# Power.net
KiCad netlist of a schematic drawn in Altium Designer
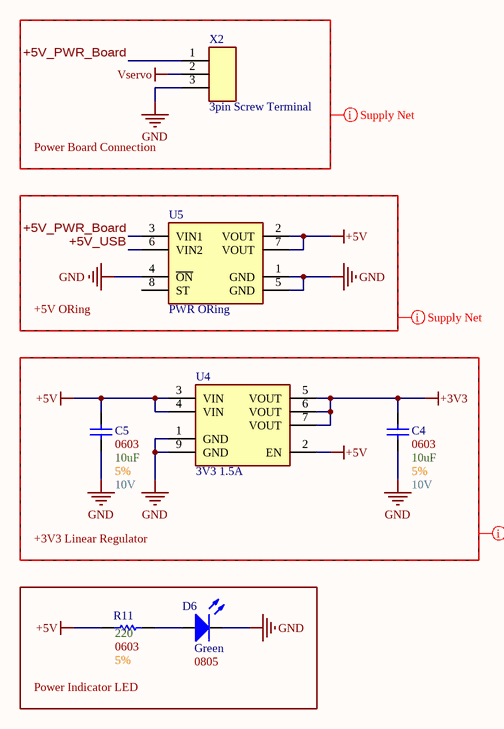
[diagram p0: Power.SchDoc]

(export (version "E")
  (design (tool "Eeschema 10.0.6"))
  (components
    (comp (ref "C4")
      (value "[Cap] SMD Nonpolarized")
      (footprint "[Cap] SMD 0603")
      (fields
        (field (name "SIZE PACKAGE") "0603")
        (field (name "CAPACITANCE") "10uF")
        (field (name "VOLTAGE") "10V")
        (field (name "TOLERANCE") "5%")
      )
      (libsource (lib "RADM Components") (part "[Cap] SMD Nonpolarized"))
    )
    (comp (ref "C5")
      (value "[Cap] SMD Nonpolarized")
      (footprint "[Cap] SMD 0603")
      (fields
        (field (name "SIZE PACKAGE") "0603")
        (field (name "CAPACITANCE") "10uF")
        (field (name "VOLTAGE") "10V")
        (field (name "TOLERANCE") "5%")
      )
      (libsource (lib "RADM Components") (part "[Cap] SMD Nonpolarized"))
    )
    (comp (ref "D6")
      (value "SMD LED")
      (footprint "[LED] SMD 0805")
      (description "Generic")
      (fields (field (name "COLOR") "Green") (field (name "SIZE PACKAGE") "0805"))
      (libsource (lib "RADM Components") (part "[LED] SMD"))
    )
    (comp (ref "R11")
      (value "[Res] SMD Resistor")
      (footprint "[Res] SMD 0603")
      (description "Generic")
      (fields
        (field (name "RESISTANCE") "220")
        (field (name "SIZE PACKAGE") "0603")
        (field (name "TOLERANCE") "5%")
      )
      (libsource (lib "RADM Components") (part "[Res] SMD Resistor"))
    )
    (comp (ref "U4")
      (value "3V3 1.5A")
      (footprint "[Reg Lin] 3V3 Regulator 1.5A")
      (description "AP7362A-33SP-13")
      (libsource (lib "RADM Components") (part "[Reg Lin] 3V3 Regulator 1.5A"))
    )
    (comp (ref "U5")
      (value "PWR ORing")
      (footprint "[IC] Power ORing Controller")
      (libsource (lib "RADM Components") (part "[IC] Power ORing Controller"))
    )
    (comp (ref "X2")
      (value "3pin Screw Terminal")
      (footprint "[Screw Terminal] 3pin 5mm")
      (libsource (lib "RADM Connectors") (part "[Screw Terminal] 3pin"))
    )
  )
  (nets
    (net (code "1") (name "+3V3") (class "Default")
      (node (ref "C4") (pin "2") (pinfunction "2_2") (pintype "passive"))
      (node (ref "U4") (pin "5") (pinfunction "VOUT_5") (pintype "passive"))
      (node (ref "U4") (pin "6") (pinfunction "VOUT_6") (pintype "passive"))
      (node (ref "U4") (pin "7") (pinfunction "VOUT_7") (pintype "passive"))
    )
    (net (code "2") (name "+5V") (class "Default")
      (node (ref "C5") (pin "2") (pinfunction "2_2") (pintype "passive"))
      (node (ref "R11") (pin "2") (pinfunction "2_2") (pintype "passive"))
      (node (ref "U4") (pin "2") (pinfunction "EN_2") (pintype "passive"))
      (node (ref "U4") (pin "3") (pinfunction "VIN_3") (pintype "passive"))
      (node (ref "U4") (pin "4") (pinfunction "VIN_4") (pintype "passive"))
      (node (ref "U5") (pin "2") (pinfunction "VOUT_2") (pintype "passive"))
      (node (ref "U5") (pin "7") (pinfunction "VOUT_7") (pintype "passive"))
    )
    (net (code "3") (name "/+5V_PWR_Board") (class "Default")
      (node (ref "U5") (pin "3") (pinfunction "VIN1_3") (pintype "passive"))
      (node (ref "X2") (pin "1") (pintype "power_in"))
    )
    (net (code "4") (name "/+5V_USB") (class "Default")
      (node (ref "U5") (pin "6") (pinfunction "VIN2_6") (pintype "passive"))
    )
    (net (code "5") (name "GND") (class "Default")
      (node (ref "C4") (pin "1") (pinfunction "1_1") (pintype "passive"))
      (node (ref "C5") (pin "1") (pinfunction "1_1") (pintype "passive"))
      (node (ref "D6") (pin "2") (pinfunction "Cathode_2") (pintype "passive"))
      (node (ref "U4") (pin "1") (pinfunction "GND_1") (pintype "passive"))
      (node (ref "U4") (pin "9") (pinfunction "GND_9") (pintype "passive"))
      (node (ref "U5") (pin "1") (pinfunction "GND_1") (pintype "passive"))
      (node (ref "U5") (pin "4") (pinfunction "~{ON}_4") (pintype "passive"))
      (node (ref "U5") (pin "5") (pinfunction "GND_5") (pintype "passive"))
      (node (ref "X2") (pin "3") (pintype "power_in"))
    )
    (net (code "6") (name "Net-(D6-Anode)") (class "Default")
      (node (ref "D6") (pin "1") (pinfunction "Anode_1") (pintype "passive"))
      (node (ref "R11") (pin "1") (pinfunction "1_1") (pintype "passive"))
    )
    (net (code "7") (name "Vservo") (class "Default") (node (ref "X2") (pin "2") (pintype "power_in")))
    (net (code "8") (name "unconnected-(U5-ST-Pad8)") (class "Default")
      (node (ref "U5") (pin "8") (pinfunction "ST_8") (pintype "passive"))
    )
  )
)
